# 2_4GHandShank.net
KiCad netlist of a schematic drawn in Altium Designer
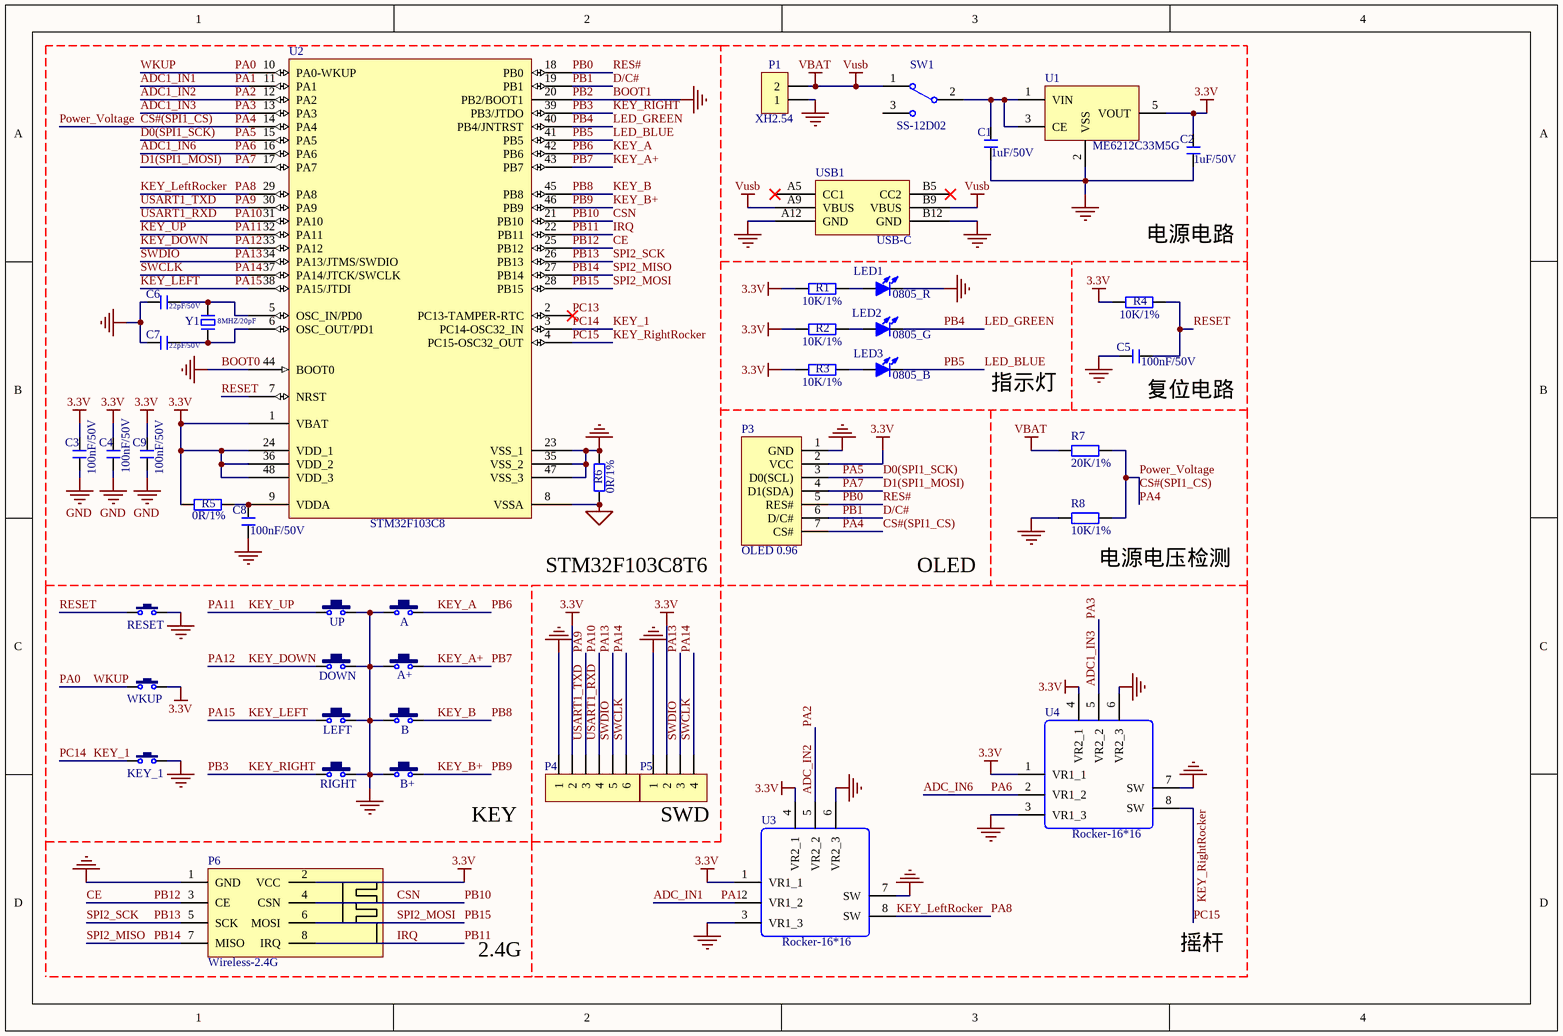
[diagram p0: 原理图_2.4GHandShank.SchDoc]

(export (version "E")
  (design (tool "Eeschema 10.0.6"))
  (components
    (comp (ref "A")
      (value "6x6x5")
      (footprint "KEY-6*6*8")
      (description "直插6x6轻触开关")
      (fields (field (name "版权归属") "源创客"))
      (libsource (lib "原理图库_2.4GHandShank") (part "TSW DIP-6x6"))
    )
    (comp (ref "A+")
      (value "6x6x5")
      (footprint "KEY-6*6*8")
      (description "直插6x6轻触开关")
      (fields (field (name "版权归属") "源创客"))
      (libsource (lib "原理图库_2.4GHandShank") (part "TSW DIP-6x6"))
    )
    (comp (ref "B")
      (value "6x6x5")
      (footprint "KEY-6*6*8")
      (description "直插6x6轻触开关")
      (fields (field (name "版权归属") "源创客"))
      (libsource (lib "原理图库_2.4GHandShank") (part "TSW DIP-6x6"))
    )
    (comp (ref "B+")
      (value "6x6x5")
      (footprint "KEY-6*6*8")
      (description "直插6x6轻触开关")
      (fields (field (name "版权归属") "源创客"))
      (libsource (lib "原理图库_2.4GHandShank") (part "TSW DIP-6x6"))
    )
    (comp (ref "C1")
      (value "1uF/50V")
      (footprint "C 0603_M")
      (description "无极性贴片电容")
      (fields (field (name "版权归属") "源创客"))
      (libsource (lib "原理图库_2.4GHandShank") (part "C"))
    )
    (comp (ref "C2")
      (value "1uF/50V")
      (footprint "C 0603_M")
      (description "无极性贴片电容")
      (fields (field (name "版权归属") "源创客"))
      (libsource (lib "原理图库_2.4GHandShank") (part "C"))
    )
    (comp (ref "C3")
      (value "100nF/50V")
      (footprint "C 0603_M")
      (description "无极性贴片电容")
      (fields (field (name "版权归属") "源创客"))
      (libsource (lib "原理图库_2.4GHandShank") (part "C"))
    )
    (comp (ref "C4")
      (value "100nF/50V")
      (footprint "C 0603_M")
      (description "无极性贴片电容")
      (fields (field (name "版权归属") "源创客"))
      (libsource (lib "原理图库_2.4GHandShank") (part "C"))
    )
    (comp (ref "C5")
      (value "100nF/50V")
      (footprint "C 0603_M")
      (description "无极性贴片电容")
      (fields (field (name "版权归属") "源创客"))
      (libsource (lib "原理图库_2.4GHandShank") (part "C"))
    )
    (comp (ref "C6")
      (value "22pF/50V")
      (footprint "C 0603_M")
      (description "无极性贴片电容")
      (fields (field (name "版权归属") "源创客"))
      (libsource (lib "原理图库_2.4GHandShank") (part "C"))
    )
    (comp (ref "C7")
      (value "22pF/50V")
      (footprint "C 0603_M")
      (description "无极性贴片电容")
      (fields (field (name "版权归属") "源创客"))
      (libsource (lib "原理图库_2.4GHandShank") (part "C"))
    )
    (comp (ref "C8")
      (value "100nF/50V")
      (footprint "C 0603_M")
      (description "无极性贴片电容")
      (fields (field (name "版权归属") "源创客"))
      (libsource (lib "原理图库_2.4GHandShank") (part "C"))
    )
    (comp (ref "C9")
      (value "100nF/50V")
      (footprint "C 0603_M")
      (description "无极性贴片电容")
      (fields (field (name "版权归属") "源创客"))
      (libsource (lib "原理图库_2.4GHandShank") (part "C"))
    )
    (comp (ref "DOWN")
      (value "6x6x5")
      (footprint "KEY-6*6*8")
      (description "直插6x6轻触开关")
      (fields (field (name "版权归属") "源创客"))
      (libsource (lib "") (part "TSW DIP-6x6_1"))
    )
    (comp (ref "KEY_1")
      (value "3x6x5")
      (footprint "TSW SMD-3*6*2.5")
      (description "3x6轻触开关")
      (fields (field (name "版权归属") "源创客"))
      (libsource (lib "原理图库_2.4GHandShank") (part "TSW 3x6"))
    )
    (comp (ref "LED1")
      (value "0805_R")
      (footprint "LED 0805R")
      (description "贴片LED")
      (fields (field (name "版权归属") "源创客"))
      (libsource (lib "原理图库_2.4GHandShank") (part "LED-SMD"))
    )
    (comp (ref "LED2")
      (value "0805_G")
      (footprint "LED 0805G")
      (description "贴片LED")
      (fields (field (name "版权归属") "源创客"))
      (libsource (lib "原理图库_2.4GHandShank") (part "LED-SMD"))
    )
    (comp (ref "LED3")
      (value "0805_B")
      (footprint "LED 0805B")
      (description "贴片LED")
      (fields (field (name "版权归属") "源创客"))
      (libsource (lib "原理图库_2.4GHandShank") (part "LED-SMD"))
    )
    (comp (ref "LEFT")
      (value "6x6x5")
      (footprint "KEY-6*6*8")
      (description "直插6x6轻触开关")
      (fields (field (name "版权归属") "源创客"))
      (libsource (lib "") (part "TSW DIP-6x6_1"))
    )
    (comp (ref "P1")
      (value "XH2.54")
      (footprint "XH2.54-WI-2P")
      (description "2P接插件")
      (fields (field (name "版权归属") "源创客"))
      (libsource (lib "原理图库_2.4GHandShank") (part "Header 2"))
    )
    (comp (ref "P3")
      (value "OLED 0.96")
      (footprint "OLED 0.96")
      (fields (field (name "版权归属") "源创客"))
      (libsource (lib "原理图库_2.4GHandShank") (part "OLED 0.96"))
    )
    (comp (ref "P4")
      (value "HDR-1X6")
      (footprint "HDR2.54-M-LI-6P")
      (description "6P接插件")
      (fields (field (name "版权归属") "源创客"))
      (libsource (lib "原理图库_2.4GHandShank") (part "Header 6"))
    )
    (comp (ref "P5")
      (value "HDR-1X4")
      (footprint "HDR2.54-LI-4P")
      (description "4P接插件")
      (fields (field (name "版权归属") "源创客"))
      (libsource (lib "原理图库_2.4GHandShank") (part "Header 4"))
    )
    (comp (ref "P6")
      (value "Wireless-2.4G")
      (footprint "Wireless-2.4G")
      (description "2.4GWiFI模块")
      (libsource (lib "原理图库_2.4GHandShank") (part "Wireless-2.4G"))
    )
    (comp (ref "R1")
      (value "10K/1%")
      (footprint "R 0603_M")
      (description "贴片电阻")
      (fields (field (name "版权归属") "源创客"))
      (libsource (lib "原理图库_2.4GHandShank") (part "R"))
    )
    (comp (ref "R2")
      (value "10K/1%")
      (footprint "R 0603_M")
      (description "贴片电阻")
      (fields (field (name "版权归属") "源创客"))
      (libsource (lib "原理图库_2.4GHandShank") (part "R"))
    )
    (comp (ref "R3")
      (value "10K/1%")
      (footprint "R 0603_M")
      (description "贴片电阻")
      (fields (field (name "版权归属") "源创客"))
      (libsource (lib "原理图库_2.4GHandShank") (part "R"))
    )
    (comp (ref "R4")
      (value "10K/1%")
      (footprint "R 0603_M")
      (description "贴片电阻")
      (fields (field (name "版权归属") "源创客"))
      (libsource (lib "原理图库_2.4GHandShank") (part "R"))
    )
    (comp (ref "R5")
      (value "0R/1%")
      (footprint "R 0603_M")
      (description "贴片电阻")
      (fields (field (name "版权归属") "源创客"))
      (libsource (lib "原理图库_2.4GHandShank") (part "R"))
    )
    (comp (ref "R6")
      (value "0R/1%")
      (footprint "R 0603_M")
      (description "贴片电阻")
      (fields (field (name "版权归属") "源创客"))
      (libsource (lib "原理图库_2.4GHandShank") (part "R"))
    )
    (comp (ref "R7")
      (value "20K/1%")
      (footprint "R 0603_M")
      (description "贴片电阻")
      (fields (field (name "版权归属") "源创客"))
      (libsource (lib "原理图库_2.4GHandShank") (part "R"))
    )
    (comp (ref "R8")
      (value "10K/1%")
      (footprint "R 0603_M")
      (description "贴片电阻")
      (fields (field (name "版权归属") "源创客"))
      (libsource (lib "原理图库_2.4GHandShank") (part "R"))
    )
    (comp (ref "RESET")
      (value "3x6x5")
      (footprint "TSW SMD-3*6*2.5")
      (description "3x6轻触开关")
      (fields (field (name "版权归属") "源创客"))
      (libsource (lib "原理图库_2.4GHandShank") (part "TSW 3x6"))
    )
    (comp (ref "RIGHT")
      (value "6x6x5")
      (footprint "KEY-6*6*8")
      (description "直插6x6轻触开关")
      (fields (field (name "版权归属") "源创客"))
      (libsource (lib "") (part "TSW DIP-6x6_1"))
    )
    (comp (ref "SW1")
      (value "SS-12D02")
      (footprint "SS-12D02")
      (description "1路波动开关")
      (fields (field (name "版权归属") "源创客"))
      (libsource (lib "原理图库_2.4GHandShank") (part "SSW-1P"))
    )
    (comp (ref "U1")
      (value "ME6212C33M5G")
      (footprint "SOT23-5M")
      (description "低压差线性稳压器")
      (libsource (lib "原理图库_2.4GHandShank") (part "ME6212C33M5G"))
    )
    (comp (ref "U2")
      (value "STM32F103C8")
      (footprint "LQFP48 7X7_M")
      (description "Flaah:64/RAM:20/IO:36")
      (fields (field (name "版权归属") "源创客"))
      (libsource (lib "原理图库_2.4GHandShank") (part "STM32F103C8"))
    )
    (comp (ref "U3")
      (value "Rocker-16*16")
      (footprint "Rocker")
      (description "摇杆16*16")
      (libsource (lib "原理图库_2.4GHandShank") (part "Rocker"))
    )
    (comp (ref "U4")
      (value "Rocker-16*16")
      (footprint "Rocker")
      (description "摇杆16*16")
      (libsource (lib "原理图库_2.4GHandShank") (part "Rocker"))
    )
    (comp (ref "UP")
      (value "6x6x5")
      (footprint "KEY-6*6*8")
      (description "直插6x6轻触开关")
      (fields (field (name "版权归属") "源创客"))
      (libsource (lib "") (part "TSW DIP-6x6_1"))
    )
    (comp (ref "USB1")
      (value "USB-C")
      (footprint "USB-C-SMD_6P")
      (description "USB-C型母接口 6Pin")
      (fields (field (name "版权归属") "源创客"))
      (libsource (lib "原理图库_2.4GHandShank") (part "USB-C 6P"))
    )
    (comp (ref "WKUP")
      (value "3x6x5")
      (footprint "TSW SMD-3*6*2.5")
      (description "3x6轻触开关")
      (fields (field (name "版权归属") "源创客"))
      (libsource (lib "原理图库_2.4GHandShank") (part "TSW 3x6"))
    )
    (comp (ref "Y1")
      (value "8MHZ/20pF")
      (footprint "OSC HC-49S")
      (description "2脚无源脚晶振")
      (fields (field (name "版权归属") "源创客"))
      (libsource (lib "原理图库_2.4GHandShank") (part "XTAL-2P"))
    )
  )
  (nets
    (net (code "1") (name "/ADC1_IN1") (class "Default")
      (node (ref "U2") (pin "11") (pinfunction "PA1_11") (pintype "bidirectional"))
      (node (ref "U3") (pin "2") (pinfunction "VR1_2_2") (pintype "passive"))
    )
    (net (code "2") (name "/ADC1_IN2") (class "Default")
      (node (ref "U2") (pin "12") (pinfunction "PA2_12") (pintype "bidirectional"))
      (node (ref "U3") (pin "5") (pinfunction "VR2_2_5") (pintype "passive"))
    )
    (net (code "3") (name "/ADC1_IN3") (class "Default")
      (node (ref "U2") (pin "13") (pinfunction "PA3_13") (pintype "bidirectional"))
      (node (ref "U4") (pin "5") (pinfunction "VR2_2_5") (pintype "passive"))
    )
    (net (code "4") (name "/ADC1_IN6") (class "Default")
      (node (ref "U2") (pin "16") (pinfunction "PA6_16") (pintype "bidirectional"))
      (node (ref "U4") (pin "2") (pinfunction "VR1_2_2") (pintype "passive"))
    )
    (net (code "5") (name "/CE") (class "Default")
      (node (ref "P6") (pin "3") (pinfunction "CE_3") (pintype "passive"))
      (node (ref "U2") (pin "25") (pinfunction "PB12_25") (pintype "bidirectional"))
    )
    (net (code "6") (name "/CS#(SPI1_CS)") (class "Default")
      (node (ref "P3") (pin "7") (pinfunction "CS#_7") (pintype "passive"))
      (node (ref "R7") (pin "2") (pinfunction "2_2") (pintype "passive"))
      (node (ref "R8") (pin "2") (pinfunction "2_2") (pintype "passive"))
      (node (ref "U2") (pin "14") (pinfunction "PA4_14") (pintype "bidirectional"))
    )
    (net (code "7") (name "/CSN") (class "Default")
      (node (ref "P6") (pin "4") (pinfunction "CSN_4") (pintype "passive"))
      (node (ref "U2") (pin "21") (pinfunction "PB10_21") (pintype "bidirectional"))
    )
    (net (code "8") (name "/D0(SPI1_SCK)") (class "Default")
      (node (ref "P3") (pin "3") (pinfunction "D0(SCL)_3") (pintype "passive"))
      (node (ref "U2") (pin "15") (pinfunction "PA5_15") (pintype "bidirectional"))
    )
    (net (code "9") (name "/D1(SPI1_MOSI)") (class "Default")
      (node (ref "P3") (pin "4") (pinfunction "D1(SDA)_4") (pintype "passive"))
      (node (ref "U2") (pin "17") (pinfunction "PA7_17") (pintype "bidirectional"))
    )
    (net (code "10") (name "/D{slash}C#") (class "Default")
      (node (ref "P3") (pin "6") (pinfunction "D/C#_6") (pintype "passive"))
      (node (ref "U2") (pin "19") (pinfunction "PB1_19") (pintype "bidirectional"))
    )
    (net (code "11") (name "/IRQ") (class "Default")
      (node (ref "P6") (pin "8") (pinfunction "IRQ_8") (pintype "passive"))
      (node (ref "U2") (pin "22") (pinfunction "PB11_22") (pintype "bidirectional"))
    )
    (net (code "12") (name "/KEY_1") (class "Default")
      (node (ref "KEY_1") (pin "1") (pinfunction "1_1") (pintype "passive"))
      (node (ref "U2") (pin "3") (pinfunction "PC14-OSC32_IN_3") (pintype "bidirectional"))
    )
    (net (code "13") (name "/KEY_A") (class "Default")
      (node (ref "A") (pin "2") (pinfunction "2_2") (pintype "passive"))
      (node (ref "U2") (pin "42") (pinfunction "PB6_42") (pintype "bidirectional"))
    )
    (net (code "14") (name "/KEY_A+") (class "Default")
      (node (ref "A+") (pin "2") (pinfunction "2_2") (pintype "passive"))
      (node (ref "U2") (pin "43") (pinfunction "PB7_43") (pintype "bidirectional"))
    )
    (net (code "15") (name "/KEY_B") (class "Default")
      (node (ref "B") (pin "2") (pinfunction "2_2") (pintype "passive"))
      (node (ref "U2") (pin "45") (pinfunction "PB8_45") (pintype "bidirectional"))
    )
    (net (code "16") (name "/KEY_B+") (class "Default")
      (node (ref "B+") (pin "2") (pinfunction "2_2") (pintype "passive"))
      (node (ref "U2") (pin "46") (pinfunction "PB9_46") (pintype "bidirectional"))
    )
    (net (code "17") (name "/KEY_DOWN") (class "Default")
      (node (ref "DOWN") (pin "2") (pinfunction "2_2") (pintype "passive"))
      (node (ref "U2") (pin "33") (pinfunction "PA12_33") (pintype "bidirectional"))
    )
    (net (code "18") (name "/KEY_LEFT") (class "Default")
      (node (ref "LEFT") (pin "2") (pinfunction "2_2") (pintype "passive"))
      (node (ref "U2") (pin "38") (pinfunction "PA15/JTDI_38") (pintype "bidirectional"))
    )
    (net (code "19") (name "/KEY_LeftRocker") (class "Default")
      (node (ref "U2") (pin "29") (pinfunction "PA8_29") (pintype "bidirectional"))
      (node (ref "U3") (pin "8") (pinfunction "SW_8") (pintype "passive"))
    )
    (net (code "20") (name "/KEY_RIGHT") (class "Default")
      (node (ref "RIGHT") (pin "2") (pinfunction "2_2") (pintype "passive"))
      (node (ref "U2") (pin "39") (pinfunction "PB3/JTDO_39") (pintype "bidirectional"))
    )
    (net (code "21") (name "/KEY_RightRocker") (class "Default")
      (node (ref "U2") (pin "4") (pinfunction "PC15-OSC32_OUT_4") (pintype "bidirectional"))
      (node (ref "U4") (pin "8") (pinfunction "SW_8") (pintype "passive"))
    )
    (net (code "22") (name "/KEY_UP") (class "Default")
      (node (ref "U2") (pin "32") (pinfunction "PA11_32") (pintype "bidirectional"))
      (node (ref "UP") (pin "2") (pinfunction "2_2") (pintype "passive"))
    )
    (net (code "23") (name "/LED_BLUE") (class "Default")
      (node (ref "LED3") (pin "2") (pinfunction "K_2") (pintype "passive"))
      (node (ref "U2") (pin "41") (pinfunction "PB5_41") (pintype "bidirectional"))
    )
    (net (code "24") (name "/LED_GREEN") (class "Default")
      (node (ref "LED2") (pin "2") (pinfunction "K_2") (pintype "passive"))
      (node (ref "U2") (pin "40") (pinfunction "PB4/JNTRST_40") (pintype "bidirectional"))
    )
    (net (code "25") (name "/PA0") (class "Default")
      (node (ref "U2") (pin "10") (pinfunction "PA0-WKUP_10") (pintype "bidirectional"))
      (node (ref "WKUP") (pin "1") (pinfunction "1_1") (pintype "passive"))
    )
    (net (code "26") (name "/PA9") (class "Default")
      (node (ref "P4") (pin "3") (pinfunction "3_3") (pintype "passive"))
      (node (ref "U2") (pin "30") (pinfunction "PA9_30") (pintype "bidirectional"))
    )
    (net (code "27") (name "/PA10") (class "Default")
      (node (ref "P4") (pin "4") (pinfunction "4_4") (pintype "passive"))
      (node (ref "U2") (pin "31") (pinfunction "PA10_31") (pintype "bidirectional"))
    )
    (net (code "28") (name "/PA13") (class "Default")
      (node (ref "P4") (pin "5") (pinfunction "5_5") (pintype "passive"))
      (node (ref "P5") (pin "3") (pinfunction "3_3") (pintype "passive"))
      (node (ref "U2") (pin "34") (pinfunction "PA13/JTMS/SWDIO_34") (pintype "bidirectional"))
    )
    (net (code "29") (name "/PA14") (class "Default")
      (node (ref "P4") (pin "6") (pinfunction "6_6") (pintype "passive"))
      (node (ref "P5") (pin "4") (pinfunction "4_4") (pintype "passive"))
      (node (ref "U2") (pin "37") (pinfunction "PA14/JTCK/SWCLK_37") (pintype "bidirectional"))
    )
    (net (code "30") (name "/PB0") (class "Default")
      (node (ref "P3") (pin "5") (pinfunction "RES#_5") (pintype "passive"))
      (node (ref "U2") (pin "18") (pinfunction "PB0_18") (pintype "bidirectional"))
    )
    (net (code "31") (name "/PB13") (class "Default")
      (node (ref "P6") (pin "5") (pinfunction "SCK_5") (pintype "passive"))
      (node (ref "U2") (pin "26") (pinfunction "PB13_26") (pintype "bidirectional"))
    )
    (net (code "32") (name "/PB14") (class "Default")
      (node (ref "P6") (pin "7") (pinfunction "MISO_7") (pintype "passive"))
      (node (ref "U2") (pin "27") (pinfunction "PB14_27") (pintype "bidirectional"))
    )
    (net (code "33") (name "/PB15") (class "Default")
      (node (ref "P6") (pin "6") (pinfunction "MOSI_6") (pintype "passive"))
      (node (ref "U2") (pin "28") (pinfunction "PB15_28") (pintype "bidirectional"))
    )
    (net (code "34") (name "/PC13") (class "Default")
      (node (ref "U2") (pin "2") (pinfunction "PC13-TAMPER-RTC_2") (pintype "bidirectional+no_connect"))
    )
    (net (code "35") (name "/RESET") (class "Default")
      (node (ref "C5") (pin "2") (pinfunction "2_2") (pintype "passive"))
      (node (ref "R4") (pin "1") (pinfunction "1_1") (pintype "passive"))
      (node (ref "RESET") (pin "1") (pinfunction "1_1") (pintype "passive"))
      (node (ref "U2") (pin "7") (pinfunction "NRST_7") (pintype "bidirectional"))
    )
    (net (code "36") (name "3.3V") (class "Default")
      (node (ref "C2") (pin "2") (pinfunction "2_2") (pintype "passive"))
      (node (ref "C3") (pin "2") (pinfunction "2_2") (pintype "passive"))
      (node (ref "C4") (pin "2") (pinfunction "2_2") (pintype "passive"))
      (node (ref "C9") (pin "2") (pinfunction "2_2") (pintype "passive"))
      (node (ref "P3") (pin "2") (pinfunction "VCC_2") (pintype "passive"))
      (node (ref "P4") (pin "2") (pinfunction "2_2") (pintype "passive"))
      (node (ref "P5") (pin "2") (pinfunction "2_2") (pintype "passive"))
      (node (ref "P6") (pin "2") (pinfunction "VCC_2") (pintype "passive"))
      (node (ref "R1") (pin "2") (pinfunction "2_2") (pintype "passive"))
      (node (ref "R2") (pin "2") (pinfunction "2_2") (pintype "passive"))
      (node (ref "R3") (pin "2") (pinfunction "2_2") (pintype "passive"))
      (node (ref "R4") (pin "2") (pinfunction "2_2") (pintype "passive"))
      (node (ref "R5") (pin "1") (pinfunction "1_1") (pintype "passive"))
      (node (ref "U1") (pin "5") (pinfunction "VOUT_5") (pintype "passive"))
      (node (ref "U2") (pin "1") (pinfunction "VBAT_1") (pintype "power_in"))
      (node (ref "U2") (pin "24") (pinfunction "VDD_1_24") (pintype "power_in"))
      (node (ref "U2") (pin "36") (pinfunction "VDD_2_36") (pintype "power_in"))
      (node (ref "U2") (pin "48") (pinfunction "VDD_3_48") (pintype "power_in"))
      (node (ref "U3") (pin "1") (pinfunction "VR1_1_1") (pintype "passive"))
      (node (ref "U3") (pin "4") (pinfunction "VR2_1_4") (pintype "passive"))
      (node (ref "U4") (pin "1") (pinfunction "VR1_1_1") (pintype "passive"))
      (node (ref "U4") (pin "4") (pinfunction "VR2_1_4") (pintype "passive"))
      (node (ref "WKUP") (pin "2") (pinfunction "2_2") (pintype "passive"))
    )
    (net (code "37") (name "AGND") (class "Default")
      (node (ref "R6") (pin "1") (pinfunction "1_1") (pintype "passive"))
      (node (ref "U2") (pin "8") (pinfunction "VSSA_8") (pintype "power_in"))
    )
    (net (code "38") (name "GND") (class "Default")
      (node (ref "A") (pin "1") (pinfunction "1_1") (pintype "passive"))
      (node (ref "A+") (pin "1") (pinfunction "1_1") (pintype "passive"))
      (node (ref "B") (pin "1") (pinfunction "1_1") (pintype "passive"))
      (node (ref "B+") (pin "1") (pinfunction "1_1") (pintype "passive"))
      (node (ref "C1") (pin "1") (pinfunction "1_1") (pintype "passive"))
      (node (ref "C2") (pin "1") (pinfunction "1_1") (pintype "passive"))
      (node (ref "C3") (pin "1") (pinfunction "1_1") (pintype "passive"))
      (node (ref "C4") (pin "1") (pinfunction "1_1") (pintype "passive"))
      (node (ref "C5") (pin "1") (pinfunction "1_1") (pintype "passive"))
      (node (ref "C6") (pin "1") (pinfunction "1_1") (pintype "passive"))
      (node (ref "C7") (pin "1") (pinfunction "1_1") (pintype "passive"))
      (node (ref "C8") (pin "1") (pinfunction "1_1") (pintype "passive"))
      (node (ref "C9") (pin "1") (pinfunction "1_1") (pintype "passive"))
      (node (ref "DOWN") (pin "1") (pinfunction "1_1") (pintype "passive"))
      (node (ref "KEY_1") (pin "2") (pinfunction "2_2") (pintype "passive"))
      (node (ref "LED1") (pin "2") (pinfunction "K_2") (pintype "passive"))
      (node (ref "LEFT") (pin "1") (pinfunction "1_1") (pintype "passive"))
      (node (ref "P1") (pin "1") (pinfunction "1_1") (pintype "passive"))
      (node (ref "P3") (pin "1") (pinfunction "GND_1") (pintype "passive"))
      (node (ref "P4") (pin "1") (pinfunction "1_1") (pintype "passive"))
      (node (ref "P5") (pin "1") (pinfunction "1_1") (pintype "passive"))
      (node (ref "P6") (pin "1") (pinfunction "GND_1") (pintype "passive"))
      (node (ref "R6") (pin "2") (pinfunction "2_2") (pintype "passive"))
      (node (ref "R8") (pin "1") (pinfunction "1_1") (pintype "passive"))
      (node (ref "RESET") (pin "2") (pinfunction "2_2") (pintype "passive"))
      (node (ref "RIGHT") (pin "1") (pinfunction "1_1") (pintype "passive"))
      (node (ref "U1") (pin "2") (pinfunction "VSS_2") (pintype "passive"))
      (node (ref "U2") (pin "20") (pinfunction "PB2/BOOT1_20") (pintype "passive"))
      (node (ref "U2") (pin "23") (pinfunction "VSS_1_23") (pintype "power_in"))
      (node (ref "U2") (pin "35") (pinfunction "VSS_2_35") (pintype "power_in"))
      (node (ref "U2") (pin "44") (pinfunction "BOOT0_44") (pintype "input"))
      (node (ref "U2") (pin "47") (pinfunction "VSS_3_47") (pintype "power_in"))
      (node (ref "U3") (pin "3") (pinfunction "VR1_3_3") (pintype "passive"))
      (node (ref "U3") (pin "6") (pinfunction "VR2_3_6") (pintype "passive"))
      (node (ref "U3") (pin "7") (pinfunction "SW_7") (pintype "passive"))
      (node (ref "U4") (pin "3") (pinfunction "VR1_3_3") (pintype "passive"))
      (node (ref "U4") (pin "6") (pinfunction "VR2_3_6") (pintype "passive"))
      (node (ref "U4") (pin "7") (pinfunction "SW_7") (pintype "passive"))
      (node (ref "UP") (pin "1") (pinfunction "1_1") (pintype "passive"))
      (node (ref "USB1") (pin "A12") (pinfunction "GND_A12") (pintype "passive"))
      (node (ref "USB1") (pin "B12") (pinfunction "GND_B12") (pintype "passive"))
    )
    (net (code "39") (name "Net-(LED1-A)") (class "Default")
      (node (ref "LED1") (pin "1") (pinfunction "A_1") (pintype "passive"))
      (node (ref "R1") (pin "1") (pinfunction "1_1") (pintype "passive"))
    )
    (net (code "40") (name "Net-(LED2-A)") (class "Default")
      (node (ref "LED2") (pin "1") (pinfunction "A_1") (pintype "passive"))
      (node (ref "R2") (pin "1") (pinfunction "1_1") (pintype "passive"))
    )
    (net (code "41") (name "Net-(LED3-A)") (class "Default")
      (node (ref "LED3") (pin "1") (pinfunction "A_1") (pintype "passive"))
      (node (ref "R3") (pin "1") (pinfunction "1_1") (pintype "passive"))
    )
    (net (code "42") (name "Net-(U1-CE)") (class "Default")
      (node (ref "C1") (pin "2") (pinfunction "2_2") (pintype "passive"))
      (node (ref "SW1") (pin "2") (pinfunction "2_2") (pintype "passive"))
      (node (ref "U1") (pin "1") (pinfunction "VIN_1") (pintype "passive"))
      (node (ref "U1") (pin "3") (pinfunction "CE_3") (pintype "passive"))
    )
    (net (code "43") (name "Net-(U2-OSC_IN{slash}PD0)") (class "Default")
      (node (ref "C6") (pin "2") (pinfunction "2_2") (pintype "passive"))
      (node (ref "U2") (pin "5") (pinfunction "OSC_IN/PD0_5") (pintype "bidirectional"))
      (node (ref "Y1") (pin "2") (pinfunction "2_2") (pintype "passive"))
    )
    (net (code "44") (name "Net-(U2-OSC_OUT{slash}PD1)") (class "Default")
      (node (ref "C7") (pin "2") (pinfunction "2_2") (pintype "passive"))
      (node (ref "U2") (pin "6") (pinfunction "OSC_OUT/PD1_6") (pintype "bidirectional"))
      (node (ref "Y1") (pin "1") (pinfunction "1_1") (pintype "passive"))
    )
    (net (code "45") (name "Net-(U2-VDDA)") (class "Default")
      (node (ref "C8") (pin "2") (pinfunction "2_2") (pintype "passive"))
      (node (ref "R5") (pin "2") (pinfunction "2_2") (pintype "passive"))
      (node (ref "U2") (pin "9") (pinfunction "VDDA_9") (pintype "power_in"))
    )
    (net (code "46") (name "VBAT") (class "Default")
      (node (ref "P1") (pin "2") (pinfunction "2_2") (pintype "passive"))
      (node (ref "R7") (pin "1") (pinfunction "1_1") (pintype "passive"))
      (node (ref "SW1") (pin "1") (pinfunction "1_1") (pintype "passive"))
      (node (ref "USB1") (pin "A9") (pinfunction "VBUS_A9") (pintype "passive"))
      (node (ref "USB1") (pin "B9") (pinfunction "VBUS_B9") (pintype "passive"))
    )
    (net (code "47") (name "unconnected-(SW1-Pad3)") (class "Default")
      (node (ref "SW1") (pin "3") (pinfunction "3_3") (pintype "passive"))
    )
    (net (code "48") (name "unconnected-(USB1-CC1-PadA5)") (class "Default")
      (node (ref "USB1") (pin "A5") (pinfunction "CC1_A5") (pintype "passive+no_connect"))
    )
    (net (code "49") (name "unconnected-(USB1-CC2-PadB5)") (class "Default")
      (node (ref "USB1") (pin "B5") (pinfunction "CC2_B5") (pintype "passive+no_connect"))
    )
  )
)
